# 5V_Power_Supply.net
KiCad netlist of a schematic drawn in Altium Designer
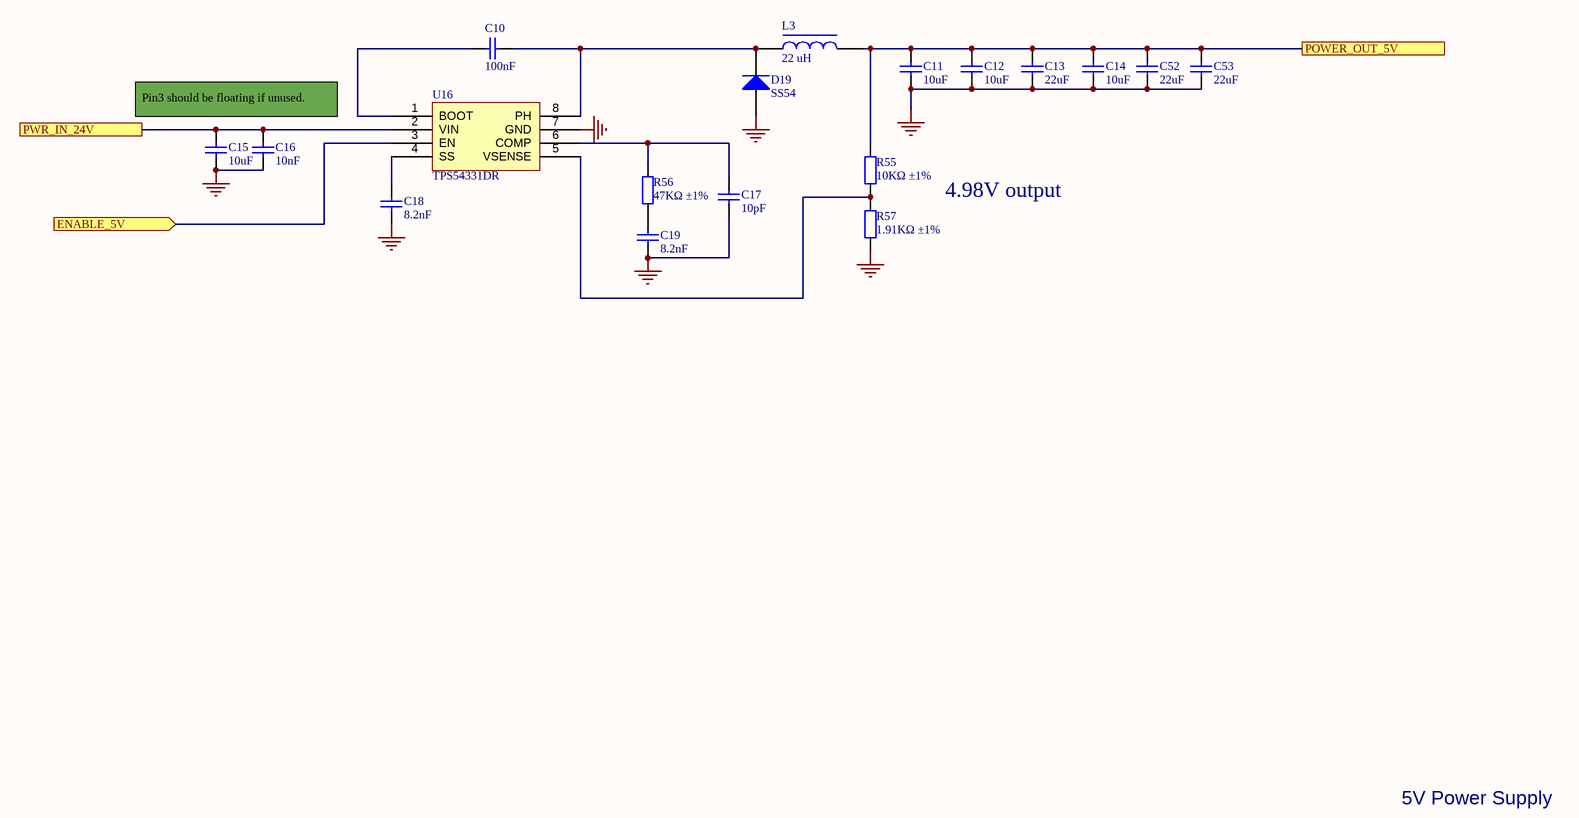
[diagram p0: 5V_Power_Supply.SchDoc]

(export (version "E")
  (design (tool "Eeschema 10.0.6"))
  (components
    (comp (ref "C10")
      (value "100nF")
      (footprint "0603_C")
      (description "50V 100nF X7R ±10% 0603 Multilayer Ceramic Capacitors MLCC - SMD/SMT ROHS")
      (fields
        (field (name "MANUFACTURER") "YAGEO")
        (field (name "MANUFACTURER PART NUMBER") "CC0603KRX7R9BB104")
      )
      (libsource (lib "Sienci_Labs") (part "0603 100nF (104) 10% 50V"))
    )
    (comp (ref "C11")
      (value "10uF")
      (footprint "1206_C")
      (description "50V 10uF X5R ±10% 1206 Multilayer Ceramic Capacitors MLCC - SMD/SMT ROHS")
      (fields
        (field (name "MANUFACTURER") "Samsung Electro-Mechanics")
        (field (name "MANUFACTURER PART NUMBER") "CL31A106KBHNNNE")
      )
      (libsource (lib "Sienci_Labs") (part "1206 10uF (106) 10% 50V"))
    )
    (comp (ref "C12")
      (value "10uF")
      (footprint "1206_C")
      (description "50V 10uF X5R ±10% 1206 Multilayer Ceramic Capacitors MLCC - SMD/SMT ROHS")
      (fields
        (field (name "MANUFACTURER") "Samsung Electro-Mechanics")
        (field (name "MANUFACTURER PART NUMBER") "CL31A106KBHNNNE")
      )
      (libsource (lib "Sienci_Labs") (part "1206 10uF (106) 10% 50V"))
    )
    (comp (ref "C13")
      (value "22uF")
      (footprint "0805_C")
      (description "25V 22uF X5R ±20% 0805 Multilayer Ceramic Capacitors MLCC - SMD/SMT ROHS")
      (fields (field (name "MANUFACTURER") "Samsung Electro-Mechanics") (field (name "TOLERANCE") "20%"))
      (libsource (lib "Sienci_Labs") (part "0805 22uF (226) 20% 25V"))
    )
    (comp (ref "C14")
      (value "10uF")
      (footprint "1206_C")
      (description "50V 10uF X5R ±10% 1206 Multilayer Ceramic Capacitors MLCC - SMD/SMT ROHS")
      (fields
        (field (name "MANUFACTURER") "Samsung Electro-Mechanics")
        (field (name "MANUFACTURER PART NUMBER") "CL31A106KBHNNNE")
      )
      (libsource (lib "Sienci_Labs") (part "1206 10uF (106) 10% 50V"))
    )
    (comp (ref "C15")
      (value "10uF")
      (footprint "1206_C")
      (description "50V 10uF X5R ±10% 1206 Multilayer Ceramic Capacitors MLCC - SMD/SMT ROHS")
      (fields
        (field (name "MANUFACTURER") "Samsung Electro-Mechanics")
        (field (name "MANUFACTURER PART NUMBER") "CL31A106KBHNNNE")
      )
      (libsource (lib "Sienci_Labs") (part "1206 10uF (106) 10% 50V"))
    )
    (comp (ref "C16")
      (value "10nF")
      (footprint "0603_C")
      (description "50V 10nF X7R ±10% 0603 Multilayer Ceramic Capacitors MLCC - SMD/SMT ROHS")
      (fields
        (field (name "MANUFACTURER") "Guangdong Fenghua Advanced Tech")
        (field (name "TOLERANCE") "10%")
      )
      (libsource (lib "Sienci_Labs") (part "0603 10nF (103) 10% 50V"))
    )
    (comp (ref "C17")
      (value "10pF")
      (footprint "0603_C")
      (description "Chip capacitors")
      (fields
        (field (name "MANUFACTURER") "Samsung Electro-Mechanics")
        (field (name "MANUFACTURER PART NUMBER") "CL10C100JB8NNNC")
      )
      (libsource (lib "Cap") (part "0603 10pF (100) 5% 50V"))
    )
    (comp (ref "C18")
      (value "8.2nF")
      (footprint "0603_C")
      (description "50V 8.2nF X7R ±10% 0603 Multilayer Ceramic Capacitors MLCC - SMD/SMT ROHS")
      (fields (field (name "MANUFACTURER") "YAGEO") (field (name "TOLERANCE") "10%"))
      (libsource (lib "Sienci_Labs") (part "0603 8.2nF (822) 10% 50V"))
    )
    (comp (ref "C19")
      (value "8.2nF")
      (footprint "0603_C")
      (description "50V 8.2nF X7R ±10% 0603 Multilayer Ceramic Capacitors MLCC - SMD/SMT ROHS")
      (fields (field (name "MANUFACTURER") "YAGEO") (field (name "TOLERANCE") "10%"))
      (libsource (lib "Sienci_Labs") (part "0603 8.2nF (822) 10% 50V"))
    )
    (comp (ref "C52")
      (value "22uF")
      (footprint "0805_C")
      (description "25V 22uF X5R ±20% 0805 Multilayer Ceramic Capacitors MLCC - SMD/SMT ROHS")
      (fields (field (name "MANUFACTURER") "Samsung Electro-Mechanics") (field (name "TOLERANCE") "20%"))
      (libsource (lib "Sienci_Labs") (part "0805 22uF (226) 20% 25V"))
    )
    (comp (ref "C53")
      (value "22uF")
      (footprint "0805_C")
      (description "25V 22uF X5R ±20% 0805 Multilayer Ceramic Capacitors MLCC - SMD/SMT ROHS")
      (fields (field (name "MANUFACTURER") "Samsung Electro-Mechanics") (field (name "TOLERANCE") "20%"))
      (libsource (lib "Sienci_Labs") (part "0805 22uF (226) 20% 25V"))
    )
    (comp (ref "D19")
      (value "SS54")
      (footprint "SMA(DO-214AC)_S1")
      (description "40V 5A 550mV@5A")
      (fields (field (name "MANUFACTURER") "MDD"))
      (libsource (lib "Diode") (part "SMA(DO-214AC) SS54"))
    )
    (comp (ref "L3")
      (value "22 uH")
      (footprint "INDPM7366X300N")
      (description "3A 22uH ±20% 130mΩ SMD,7.1x6.6x3mm Power Inductors ROHS")
      (fields
        (field (name "MANUFACTURER") "YJYCOIN")
        (field (name "MANUFACTURER PART NUMBER") "YSPI0630A-220M")
      )
      (libsource (lib "PrintNC_GRBLHAL_Breakout") (part "1206 10uH 10%"))
    )
    (comp (ref "R55")
      (value "10KΩ ±1%")
      (footprint "0603_R")
      (description "Chip resistor")
      (fields
        (field (name "MANUFACTURER") "Uniroyal Elec")
        (field (name "MANUFACTURER PART NUMBER") "0603WAF1002T5E")
      )
      (libsource (lib "Sienci_Labs") (part "0603 10K (1002) 1%"))
    )
    (comp (ref "R56")
      (value "47KΩ ±1%")
      (footprint "0603_R")
      (description "Chip resistor")
      (fields
        (field (name "MANUFACTURER") "Uniroyal Elec")
        (field (name "MANUFACTURER PART NUMBER") "0603WAF4702T5E")
      )
      (libsource (lib "RES") (part "0603 47K (4702) 1%"))
    )
    (comp (ref "R57")
      (value "1.91KΩ ±1%")
      (footprint "0603_R")
      (description "Chip resistor")
      (fields
        (field (name "MANUFACTURER") "TyoHM")
        (field (name "MANUFACTURER PART NUMBER") "RMC06031.91K1%N")
      )
      (libsource (lib "RES") (part "0603 1.91K (2001) 1%"))
    )
    (comp (ref "U16")
      (value "TPS54331DR")
      (footprint "Miscellaneous Devices LC:SOIC-8_150mil")
      (description "Switching Voltage Regulators 3A 28V In Step Down SWIFT DC/DC Cnvrtr")
      (fields (field (name "MANUFACTURER") "Texas Instruments"))
      (libsource (lib "PrintNC_GRBLHAL_Breakout") (part "TPS54331DR_[C9865]"))
    )
  )
  (nets
    (net (code "1") (name "/ENABLE_5V") (class "Default")
      (node (ref "U16") (pin "3") (pinfunction "EN_3") (pintype "passive"))
    )
    (net (code "2") (name "/POWER_OUT_5V") (class "Default")
      (node (ref "C11") (pin "2") (pinfunction "2_2") (pintype "passive"))
      (node (ref "C12") (pin "2") (pinfunction "2_2") (pintype "passive"))
      (node (ref "C13") (pin "2") (pinfunction "2_2") (pintype "passive"))
      (node (ref "C14") (pin "2") (pinfunction "2_2") (pintype "passive"))
      (node (ref "C52") (pin "2") (pinfunction "2_2") (pintype "passive"))
      (node (ref "C53") (pin "2") (pinfunction "2_2") (pintype "passive"))
      (node (ref "L3") (pin "2") (pinfunction "2_2") (pintype "passive"))
      (node (ref "R55") (pin "2") (pinfunction "2_2") (pintype "passive"))
    )
    (net (code "3") (name "/PWR_IN_24V") (class "Default")
      (node (ref "C15") (pin "2") (pinfunction "2_2") (pintype "passive"))
      (node (ref "C16") (pin "2") (pinfunction "2_2") (pintype "passive"))
      (node (ref "U16") (pin "2") (pinfunction "VIN_2") (pintype "passive"))
    )
    (net (code "4") (name "GND") (class "Default")
      (node (ref "C11") (pin "1") (pinfunction "1_1") (pintype "passive"))
      (node (ref "C12") (pin "1") (pinfunction "1_1") (pintype "passive"))
      (node (ref "C13") (pin "1") (pinfunction "1_1") (pintype "passive"))
      (node (ref "C14") (pin "1") (pinfunction "1_1") (pintype "passive"))
      (node (ref "C15") (pin "1") (pinfunction "1_1") (pintype "passive"))
      (node (ref "C16") (pin "1") (pinfunction "1_1") (pintype "passive"))
      (node (ref "C17") (pin "1") (pinfunction "1_1") (pintype "passive"))
      (node (ref "C18") (pin "1") (pinfunction "1_1") (pintype "passive"))
      (node (ref "C19") (pin "1") (pinfunction "1_1") (pintype "passive"))
      (node (ref "C52") (pin "1") (pinfunction "1_1") (pintype "passive"))
      (node (ref "C53") (pin "1") (pinfunction "1_1") (pintype "passive"))
      (node (ref "D19") (pin "1") (pinfunction "A_1") (pintype "passive"))
      (node (ref "R57") (pin "1") (pinfunction "1_1") (pintype "passive"))
      (node (ref "U16") (pin "7") (pinfunction "GND_7") (pintype "passive"))
    )
    (net (code "5") (name "Net-(C19-Pad2)") (class "Default")
      (node (ref "C19") (pin "2") (pinfunction "2_2") (pintype "passive"))
      (node (ref "R56") (pin "1") (pinfunction "1_1") (pintype "passive"))
    )
    (net (code "6") (name "Net-(D19-K)") (class "Default")
      (node (ref "C10") (pin "2") (pinfunction "2_2") (pintype "passive"))
      (node (ref "D19") (pin "2") (pinfunction "K_2") (pintype "passive"))
      (node (ref "L3") (pin "1") (pinfunction "1_1") (pintype "passive"))
      (node (ref "U16") (pin "8") (pinfunction "PH_8") (pintype "passive"))
    )
    (net (code "7") (name "Net-(U16-BOOT)") (class "Default")
      (node (ref "C10") (pin "1") (pinfunction "1_1") (pintype "passive"))
      (node (ref "U16") (pin "1") (pinfunction "BOOT_1") (pintype "passive"))
    )
    (net (code "8") (name "Net-(U16-COMP)") (class "Default")
      (node (ref "C17") (pin "2") (pinfunction "2_2") (pintype "passive"))
      (node (ref "R56") (pin "2") (pinfunction "2_2") (pintype "passive"))
      (node (ref "U16") (pin "6") (pinfunction "COMP_6") (pintype "passive"))
    )
    (net (code "9") (name "Net-(U16-SS)") (class "Default")
      (node (ref "C18") (pin "2") (pinfunction "2_2") (pintype "passive"))
      (node (ref "U16") (pin "4") (pinfunction "SS_4") (pintype "passive"))
    )
    (net (code "10") (name "Net-(U16-VSENSE)") (class "Default")
      (node (ref "R55") (pin "1") (pinfunction "1_1") (pintype "passive"))
      (node (ref "R57") (pin "2") (pinfunction "2_2") (pintype "passive"))
      (node (ref "U16") (pin "5") (pinfunction "VSENSE_5") (pintype "passive"))
    )
  )
)
